# Lab01_2020-10-19_17-25-14.net
KiCad netlist of a schematic drawn in EasyEDA
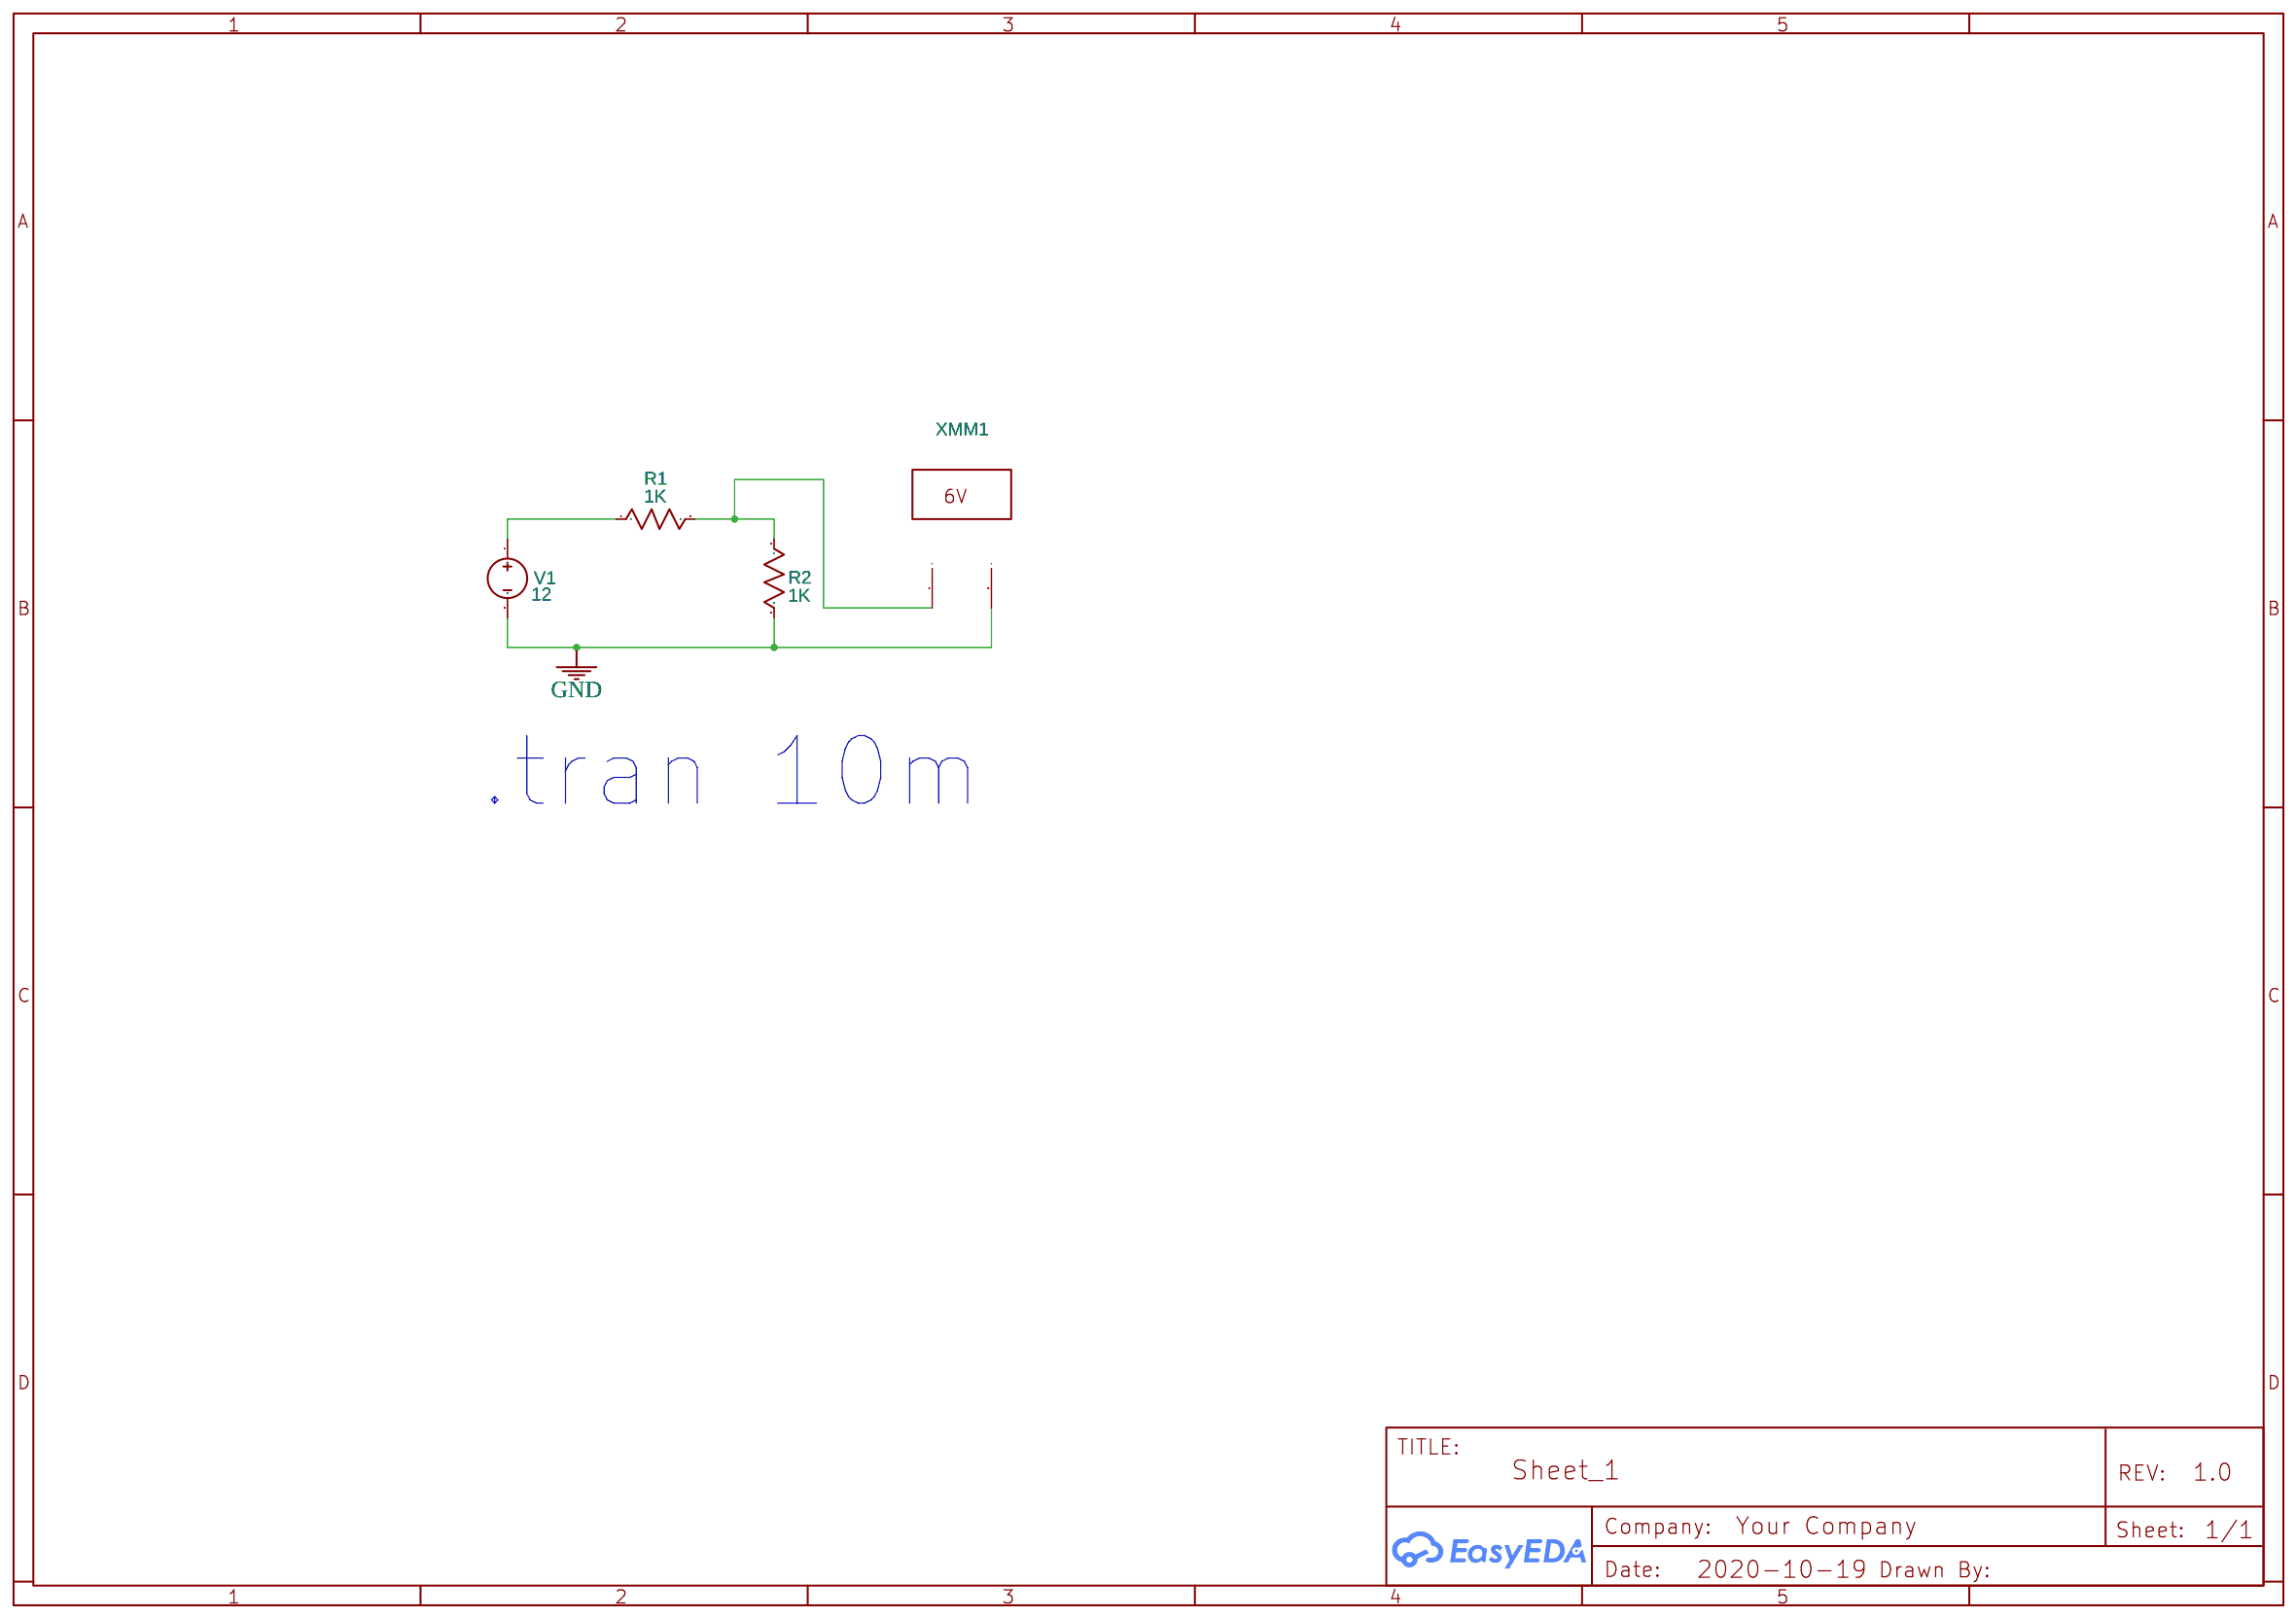
[diagram p0: schematic sheet]

(export (version "E")
  (design (tool "Eeschema 10.0.6"))
  (components
    (comp (ref "R1") (value "1K") (libsource (lib "") (part "Resistor_US_1")))
    (comp (ref "R2") (value "1K") (libsource (lib "") (part "Resistor_US")))
    (comp (ref "V1") (value "12") (libsource (lib "") (part "VDC")))
    (comp (ref "XMM1") (value "Multimeter") (libsource (lib "") (part "MULTIMETER")))
  )
  (nets
    (net (code "1") (name "GND") (class "Default")
      (node (ref "R2") (pin "2") (pinfunction "2_2") (pintype "unspecified"))
      (node (ref "V1") (pin "2") (pinfunction "2_2") (pintype "unspecified"))
      (node (ref "XMM1") (pin "2") (pinfunction "I_2") (pintype "unspecified"))
    )
    (net (code "2") (name "Net-(R1-Pad1)") (class "Default")
      (node (ref "R1") (pin "1") (pinfunction "1_1") (pintype "unspecified"))
      (node (ref "V1") (pin "1") (pinfunction "1_1") (pintype "unspecified"))
    )
    (net (code "3") (name "Net-(XMM1-+)") (class "Default")
      (node (ref "R1") (pin "2") (pinfunction "2_2") (pintype "unspecified"))
      (node (ref "R2") (pin "1") (pinfunction "1_1") (pintype "unspecified"))
      (node (ref "XMM1") (pin "1") (pinfunction "+_1") (pintype "unspecified"))
    )
  )
)
